# APM9328_MEMORY.net
KiCad netlist of a schematic drawn in Altium Designer
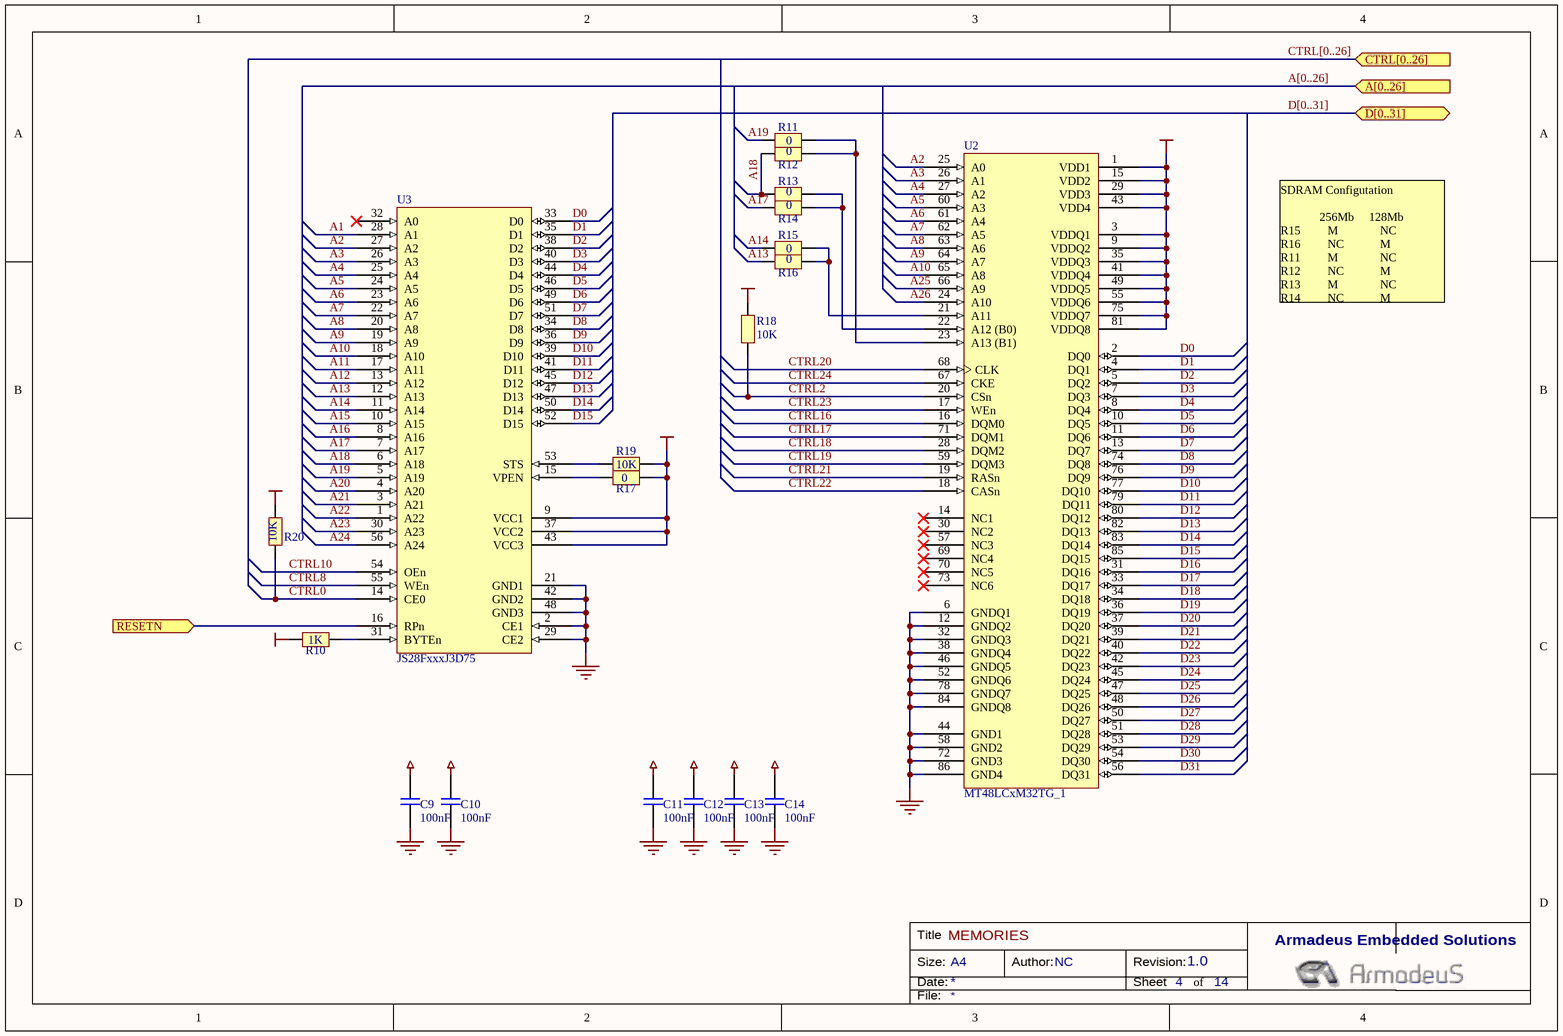
[diagram p0: APM9328_MEMORY.SchDoc]

(export (version "E")
  (design (tool "Eeschema 10.0.6"))
  (components
    (comp (ref "C9") (value "100nF") (footprint "0402") (libsource (lib "Misc") (part "Cap")))
    (comp (ref "C10") (value "100nF") (footprint "0402") (libsource (lib "Misc") (part "Cap")))
    (comp (ref "C11") (value "100nF") (footprint "0402") (libsource (lib "Misc") (part "Cap")))
    (comp (ref "C12") (value "100nF") (footprint "0402") (libsource (lib "Misc") (part "Cap")))
    (comp (ref "C13") (value "100nF") (footprint "0402") (libsource (lib "Misc") (part "Cap")))
    (comp (ref "C14") (value "100nF") (footprint "0402") (libsource (lib "Misc") (part "Cap")))
    (comp (ref "R10") (value "1K") (footprint "0402") (libsource (lib "*") (part "Res")))
    (comp (ref "R11") (value "0") (footprint "0402") (libsource (lib "*") (part "Res")))
    (comp (ref "R12") (value "0") (footprint "0402") (libsource (lib "*") (part "Res")))
    (comp (ref "R13") (value "0") (footprint "0402") (libsource (lib "*") (part "Res")))
    (comp (ref "R14") (value "0") (footprint "0402") (libsource (lib "*") (part "Res")))
    (comp (ref "R15") (value "0") (footprint "0402") (libsource (lib "*") (part "Res")))
    (comp (ref "R16") (value "0") (footprint "0402") (libsource (lib "*") (part "Res")))
    (comp (ref "R17") (value "0") (footprint "0402") (libsource (lib "*") (part "Res")))
    (comp (ref "R18") (value "10K") (footprint "0402") (libsource (lib "") (part "Res_1")))
    (comp (ref "R19") (value "10K") (footprint "0402") (libsource (lib "*") (part "Res")))
    (comp (ref "R20") (value "10K") (footprint "0402") (libsource (lib "") (part "Res_1")))
    (comp (ref "U2")
      (value "MT48LCxM32TG_1")
      (footprint "TSOP86-400")
      (description "SDRAM Memory")
      (fields (field (name "MANUFACTURER") "Micron") (field (name "PART NUMBER") "MT48LC8M32B2TG-6:GTR"))
      (libsource (lib "*") (part "MT48LCxM32TG_1"))
    )
    (comp (ref "U3")
      (value "JS28FxxxJ3D75")
      (footprint "TSOP56")
      (description "FLASH Memory")
      (fields (field (name "MANUFACTURER") "Intel") (field (name "PART NUMBER") "JS28F128J3D75"))
      (libsource (lib "*") (part "MT28FxxxJ3RG"))
    )
  )
  (nets
    (net (code "16") (name "+3V3") (class "Default")
      (node (ref "C10") (pin "2") (pintype "passive"))
      (node (ref "C11") (pin "2") (pintype "passive"))
      (node (ref "C12") (pin "2") (pintype "passive"))
      (node (ref "C13") (pin "2") (pintype "passive"))
      (node (ref "C14") (pin "2") (pintype "passive"))
      (node (ref "C9") (pin "2") (pintype "passive"))
      (node (ref "R10") (pin "1") (pintype "passive"))
      (node (ref "R17") (pin "2") (pintype "passive"))
      (node (ref "R18") (pin "2") (pintype "passive"))
      (node (ref "R19") (pin "2") (pintype "passive"))
      (node (ref "R20") (pin "2") (pintype "passive"))
      (node (ref "U2") (pin "1") (pinfunction "VDD1_1") (pintype "power_in"))
      (node (ref "U2") (pin "15") (pinfunction "VDD2_15") (pintype "power_in"))
      (node (ref "U2") (pin "29") (pinfunction "VDD3_29") (pintype "power_in"))
      (node (ref "U2") (pin "3") (pinfunction "VDDQ1_3") (pintype "power_in"))
      (node (ref "U2") (pin "35") (pinfunction "VDDQ3_35") (pintype "power_in"))
      (node (ref "U2") (pin "41") (pinfunction "VDDQ4_41") (pintype "power_in"))
      (node (ref "U2") (pin "43") (pinfunction "VDD4_43") (pintype "power_in"))
      (node (ref "U2") (pin "49") (pinfunction "VDDQ5_49") (pintype "power_in"))
      (node (ref "U2") (pin "55") (pinfunction "VDDQ6_55") (pintype "power_in"))
      (node (ref "U2") (pin "75") (pinfunction "VDDQ7_75") (pintype "power_in"))
      (node (ref "U2") (pin "81") (pinfunction "VDDQ8_81") (pintype "power_in"))
      (node (ref "U2") (pin "9") (pinfunction "VDDQ2_9") (pintype "power_in"))
      (node (ref "U3") (pin "37") (pinfunction "VCC2_37") (pintype "power_in"))
      (node (ref "U3") (pin "43") (pinfunction "VCC3_43") (pintype "power_in"))
      (node (ref "U3") (pin "9") (pinfunction "VCC1_9") (pintype "power_in"))
    )
    (net (code "17") (name "/A1") (class "Default")
      (node (ref "U3") (pin "28") (pinfunction "A1_28") (pintype "input"))
    )
    (net (code "18") (name "/A2") (class "Default")
      (node (ref "U2") (pin "25") (pinfunction "A0_25") (pintype "input"))
      (node (ref "U3") (pin "27") (pinfunction "A2_27") (pintype "input"))
    )
    (net (code "19") (name "/A3") (class "Default")
      (node (ref "U2") (pin "26") (pinfunction "A1_26") (pintype "input"))
      (node (ref "U3") (pin "26") (pinfunction "A3_26") (pintype "input"))
    )
    (net (code "20") (name "/A4") (class "Default")
      (node (ref "U2") (pin "27") (pinfunction "A2_27") (pintype "input"))
      (node (ref "U3") (pin "25") (pinfunction "A4_25") (pintype "input"))
    )
    (net (code "21") (name "/A5") (class "Default")
      (node (ref "U2") (pin "60") (pinfunction "A3_60") (pintype "input"))
      (node (ref "U3") (pin "24") (pinfunction "A5_24") (pintype "input"))
    )
    (net (code "22") (name "/A6") (class "Default")
      (node (ref "U2") (pin "61") (pinfunction "A4_61") (pintype "input"))
      (node (ref "U3") (pin "23") (pinfunction "A6_23") (pintype "input"))
    )
    (net (code "23") (name "/A7") (class "Default")
      (node (ref "U2") (pin "62") (pinfunction "A5_62") (pintype "input"))
      (node (ref "U3") (pin "22") (pinfunction "A7_22") (pintype "input"))
    )
    (net (code "24") (name "/A8") (class "Default")
      (node (ref "U2") (pin "63") (pinfunction "A6_63") (pintype "input"))
      (node (ref "U3") (pin "20") (pinfunction "A8_20") (pintype "input"))
    )
    (net (code "25") (name "/A9") (class "Default")
      (node (ref "U2") (pin "64") (pinfunction "A7_64") (pintype "input"))
      (node (ref "U3") (pin "19") (pinfunction "A9_19") (pintype "input"))
    )
    (net (code "26") (name "/A10") (class "Default")
      (node (ref "U2") (pin "65") (pinfunction "A8_65") (pintype "input"))
      (node (ref "U3") (pin "18") (pinfunction "A10_18") (pintype "input"))
    )
    (net (code "27") (name "/A11") (class "Default")
      (node (ref "U3") (pin "17") (pinfunction "A11_17") (pintype "input"))
    )
    (net (code "28") (name "/A12") (class "Default")
      (node (ref "U3") (pin "13") (pinfunction "A12_13") (pintype "input"))
    )
    (net (code "29") (name "/A13") (class "Default")
      (node (ref "R16") (pin "1") (pintype "passive"))
      (node (ref "U3") (pin "12") (pinfunction "A13_12") (pintype "input"))
    )
    (net (code "30") (name "/A14") (class "Default")
      (node (ref "R15") (pin "1") (pintype "passive"))
      (node (ref "U3") (pin "11") (pinfunction "A14_11") (pintype "input"))
    )
    (net (code "31") (name "/A15") (class "Default")
      (node (ref "U3") (pin "10") (pinfunction "A15_10") (pintype "input"))
    )
    (net (code "32") (name "/A16") (class "Default")
      (node (ref "U3") (pin "8") (pinfunction "A16_8") (pintype "input"))
    )
    (net (code "33") (name "/A17") (class "Default")
      (node (ref "R14") (pin "1") (pintype "passive"))
      (node (ref "U3") (pin "7") (pinfunction "A17_7") (pintype "input"))
    )
    (net (code "34") (name "/A18") (class "Default")
      (node (ref "R12") (pin "1") (pintype "passive"))
      (node (ref "R13") (pin "1") (pintype "passive"))
      (node (ref "U3") (pin "6") (pinfunction "A18_6") (pintype "input"))
    )
    (net (code "35") (name "/A19") (class "Default")
      (node (ref "R11") (pin "1") (pintype "passive"))
      (node (ref "U3") (pin "5") (pinfunction "A19_5") (pintype "input"))
    )
    (net (code "36") (name "/A20") (class "Default")
      (node (ref "U3") (pin "4") (pinfunction "A20_4") (pintype "input"))
    )
    (net (code "37") (name "/A21") (class "Default")
      (node (ref "U3") (pin "3") (pinfunction "A21_3") (pintype "input"))
    )
    (net (code "38") (name "/A22") (class "Default")
      (node (ref "U3") (pin "1") (pinfunction "A22_1") (pintype "input"))
    )
    (net (code "39") (name "/A23") (class "Default")
      (node (ref "U3") (pin "30") (pinfunction "A23_30") (pintype "input"))
    )
    (net (code "40") (name "/A24") (class "Default")
      (node (ref "U3") (pin "56") (pinfunction "A24_56") (pintype "input"))
    )
    (net (code "41") (name "/A25") (class "Default")
      (node (ref "U2") (pin "66") (pinfunction "A9_66") (pintype "input"))
    )
    (net (code "42") (name "/A26") (class "Default")
      (node (ref "U2") (pin "24") (pinfunction "A10_24") (pintype "input"))
    )
    (net (code "44") (name "/CTRL0") (class "Default")
      (node (ref "R20") (pin "1") (pintype "passive"))
      (node (ref "U3") (pin "14") (pinfunction "CE0_14") (pintype "input"))
    )
    (net (code "45") (name "/CTRL2") (class "Default")
      (node (ref "R18") (pin "1") (pintype "passive"))
      (node (ref "U2") (pin "20") (pinfunction "CSn_20") (pintype "input"))
    )
    (net (code "46") (name "/CTRL8") (class "Default")
      (node (ref "U3") (pin "55") (pinfunction "WEn_55") (pintype "input"))
    )
    (net (code "47") (name "/CTRL10") (class "Default")
      (node (ref "U3") (pin "54") (pinfunction "OEn_54") (pintype "input"))
    )
    (net (code "48") (name "/CTRL16") (class "Default")
      (node (ref "U2") (pin "16") (pinfunction "DQM0_16") (pintype "input"))
    )
    (net (code "49") (name "/CTRL17") (class "Default")
      (node (ref "U2") (pin "71") (pinfunction "DQM1_71") (pintype "input"))
    )
    (net (code "50") (name "/CTRL18") (class "Default")
      (node (ref "U2") (pin "28") (pinfunction "DQM2_28") (pintype "input"))
    )
    (net (code "51") (name "/CTRL19") (class "Default")
      (node (ref "U2") (pin "59") (pinfunction "DQM3_59") (pintype "input"))
    )
    (net (code "52") (name "/CTRL20") (class "Default")
      (node (ref "U2") (pin "68") (pinfunction "CLK_68") (pintype "input"))
    )
    (net (code "53") (name "/CTRL21") (class "Default")
      (node (ref "U2") (pin "19") (pinfunction "RASn_19") (pintype "input"))
    )
    (net (code "54") (name "/CTRL22") (class "Default")
      (node (ref "U2") (pin "18") (pinfunction "CASn_18") (pintype "input"))
    )
    (net (code "55") (name "/CTRL23") (class "Default")
      (node (ref "U2") (pin "17") (pinfunction "WEn_17") (pintype "input"))
    )
    (net (code "56") (name "/CTRL24") (class "Default")
      (node (ref "U2") (pin "67") (pinfunction "CKE_67") (pintype "input"))
    )
    (net (code "58") (name "/D0") (class "Default")
      (node (ref "U2") (pin "2") (pinfunction "DQ0_2") (pintype "bidirectional"))
      (node (ref "U3") (pin "33") (pinfunction "D0_33") (pintype "bidirectional"))
    )
    (net (code "59") (name "/D1") (class "Default")
      (node (ref "U2") (pin "4") (pinfunction "DQ1_4") (pintype "bidirectional"))
      (node (ref "U3") (pin "35") (pinfunction "D1_35") (pintype "bidirectional"))
    )
    (net (code "60") (name "/D2") (class "Default")
      (node (ref "U2") (pin "5") (pinfunction "DQ2_5") (pintype "bidirectional"))
      (node (ref "U3") (pin "38") (pinfunction "D2_38") (pintype "bidirectional"))
    )
    (net (code "61") (name "/D3") (class "Default")
      (node (ref "U2") (pin "7") (pinfunction "DQ3_7") (pintype "bidirectional"))
      (node (ref "U3") (pin "40") (pinfunction "D3_40") (pintype "bidirectional"))
    )
    (net (code "62") (name "/D4") (class "Default")
      (node (ref "U2") (pin "8") (pinfunction "DQ4_8") (pintype "bidirectional"))
      (node (ref "U3") (pin "44") (pinfunction "D4_44") (pintype "bidirectional"))
    )
    (net (code "63") (name "/D5") (class "Default")
      (node (ref "U2") (pin "10") (pinfunction "DQ5_10") (pintype "bidirectional"))
      (node (ref "U3") (pin "46") (pinfunction "D5_46") (pintype "bidirectional"))
    )
    (net (code "64") (name "/D6") (class "Default")
      (node (ref "U2") (pin "11") (pinfunction "DQ6_11") (pintype "bidirectional"))
      (node (ref "U3") (pin "49") (pinfunction "D6_49") (pintype "bidirectional"))
    )
    (net (code "65") (name "/D7") (class "Default")
      (node (ref "U2") (pin "13") (pinfunction "DQ7_13") (pintype "bidirectional"))
      (node (ref "U3") (pin "51") (pinfunction "D7_51") (pintype "bidirectional"))
    )
    (net (code "66") (name "/D8") (class "Default")
      (node (ref "U2") (pin "74") (pinfunction "DQ8_74") (pintype "bidirectional"))
      (node (ref "U3") (pin "34") (pinfunction "D8_34") (pintype "bidirectional"))
    )
    (net (code "67") (name "/D9") (class "Default")
      (node (ref "U2") (pin "76") (pinfunction "DQ9_76") (pintype "bidirectional"))
      (node (ref "U3") (pin "36") (pinfunction "D9_36") (pintype "bidirectional"))
    )
    (net (code "68") (name "/D10") (class "Default")
      (node (ref "U2") (pin "77") (pinfunction "DQ10_77") (pintype "bidirectional"))
      (node (ref "U3") (pin "39") (pinfunction "D10_39") (pintype "bidirectional"))
    )
    (net (code "69") (name "/D11") (class "Default")
      (node (ref "U2") (pin "79") (pinfunction "DQ11_79") (pintype "bidirectional"))
      (node (ref "U3") (pin "41") (pinfunction "D11_41") (pintype "bidirectional"))
    )
    (net (code "70") (name "/D12") (class "Default")
      (node (ref "U2") (pin "80") (pinfunction "DQ12_80") (pintype "bidirectional"))
      (node (ref "U3") (pin "45") (pinfunction "D12_45") (pintype "bidirectional"))
    )
    (net (code "71") (name "/D13") (class "Default")
      (node (ref "U2") (pin "82") (pinfunction "DQ13_82") (pintype "bidirectional"))
      (node (ref "U3") (pin "47") (pinfunction "D13_47") (pintype "bidirectional"))
    )
    (net (code "72") (name "/D14") (class "Default")
      (node (ref "U2") (pin "83") (pinfunction "DQ14_83") (pintype "bidirectional"))
      (node (ref "U3") (pin "50") (pinfunction "D14_50") (pintype "bidirectional"))
    )
    (net (code "73") (name "/D15") (class "Default")
      (node (ref "U2") (pin "85") (pinfunction "DQ15_85") (pintype "bidirectional"))
      (node (ref "U3") (pin "52") (pinfunction "D15_52") (pintype "bidirectional"))
    )
    (net (code "74") (name "/D16") (class "Default")
      (node (ref "U2") (pin "31") (pinfunction "DQ16_31") (pintype "bidirectional"))
    )
    (net (code "75") (name "/D17") (class "Default")
      (node (ref "U2") (pin "33") (pinfunction "DQ17_33") (pintype "bidirectional"))
    )
    (net (code "76") (name "/D18") (class "Default")
      (node (ref "U2") (pin "34") (pinfunction "DQ18_34") (pintype "bidirectional"))
    )
    (net (code "77") (name "/D19") (class "Default")
      (node (ref "U2") (pin "36") (pinfunction "DQ19_36") (pintype "bidirectional"))
    )
    (net (code "78") (name "/D20") (class "Default")
      (node (ref "U2") (pin "37") (pinfunction "DQ20_37") (pintype "bidirectional"))
    )
    (net (code "79") (name "/D21") (class "Default")
      (node (ref "U2") (pin "39") (pinfunction "DQ21_39") (pintype "bidirectional"))
    )
    (net (code "80") (name "/D22") (class "Default")
      (node (ref "U2") (pin "40") (pinfunction "DQ22_40") (pintype "bidirectional"))
    )
    (net (code "81") (name "/D23") (class "Default")
      (node (ref "U2") (pin "42") (pinfunction "DQ23_42") (pintype "bidirectional"))
    )
    (net (code "82") (name "/D24") (class "Default")
      (node (ref "U2") (pin "45") (pinfunction "DQ24_45") (pintype "bidirectional"))
    )
    (net (code "83") (name "/D25") (class "Default")
      (node (ref "U2") (pin "47") (pinfunction "DQ25_47") (pintype "bidirectional"))
    )
    (net (code "84") (name "/D26") (class "Default")
      (node (ref "U2") (pin "48") (pinfunction "DQ26_48") (pintype "bidirectional"))
    )
    (net (code "85") (name "/D27") (class "Default")
      (node (ref "U2") (pin "50") (pinfunction "DQ27_50") (pintype "bidirectional"))
    )
    (net (code "86") (name "/D28") (class "Default")
      (node (ref "U2") (pin "51") (pinfunction "DQ28_51") (pintype "bidirectional"))
    )
    (net (code "87") (name "/D29") (class "Default")
      (node (ref "U2") (pin "53") (pinfunction "DQ29_53") (pintype "bidirectional"))
    )
    (net (code "88") (name "/D30") (class "Default")
      (node (ref "U2") (pin "54") (pinfunction "DQ30_54") (pintype "bidirectional"))
    )
    (net (code "89") (name "/D31") (class "Default")
      (node (ref "U2") (pin "56") (pinfunction "DQ31_56") (pintype "bidirectional"))
    )
    (net (code "91") (name "/RESETN") (class "Default")
      (node (ref "U3") (pin "16") (pinfunction "RPn_16") (pintype "input"))
    )
    (net (code "92") (name "GND") (class "Default")
      (node (ref "C10") (pin "1") (pintype "passive"))
      (node (ref "C11") (pin "1") (pintype "passive"))
      (node (ref "C12") (pin "1") (pintype "passive"))
      (node (ref "C13") (pin "1") (pintype "passive"))
      (node (ref "C14") (pin "1") (pintype "passive"))
      (node (ref "C9") (pin "1") (pintype "passive"))
      (node (ref "U2") (pin "12") (pinfunction "GNDQ2_12") (pintype "power_in"))
      (node (ref "U2") (pin "32") (pinfunction "GNDQ3_32") (pintype "power_in"))
      (node (ref "U2") (pin "38") (pinfunction "GNDQ4_38") (pintype "power_in"))
      (node (ref "U2") (pin "44") (pinfunction "GND1_44") (pintype "power_in"))
      (node (ref "U2") (pin "46") (pinfunction "GNDQ5_46") (pintype "power_in"))
      (node (ref "U2") (pin "52") (pinfunction "GNDQ6_52") (pintype "power_in"))
      (node (ref "U2") (pin "58") (pinfunction "GND2_58") (pintype "power_in"))
      (node (ref "U2") (pin "6") (pinfunction "GNDQ1_6") (pintype "power_in"))
      (node (ref "U2") (pin "72") (pinfunction "GND3_72") (pintype "power_in"))
      (node (ref "U2") (pin "78") (pinfunction "GNDQ7_78") (pintype "power_in"))
      (node (ref "U2") (pin "84") (pinfunction "GNDQ8_84") (pintype "power_in"))
      (node (ref "U2") (pin "86") (pinfunction "GND4_86") (pintype "power_in"))
      (node (ref "U3") (pin "2") (pinfunction "CE1_2") (pintype "input"))
      (node (ref "U3") (pin "21") (pinfunction "GND1_21") (pintype "power_in"))
      (node (ref "U3") (pin "29") (pinfunction "CE2_29") (pintype "input"))
      (node (ref "U3") (pin "42") (pinfunction "GND2_42") (pintype "power_in"))
      (node (ref "U3") (pin "48") (pinfunction "GND3_48") (pintype "power_in"))
    )
    (net (code "93") (name "Net-(U2-A11)") (class "Default")
      (node (ref "R15") (pin "2") (pintype "passive"))
      (node (ref "R16") (pin "2") (pintype "passive"))
      (node (ref "U2") (pin "21") (pinfunction "A11_21") (pintype "input"))
    )
    (net (code "94") (name "Net-(U2-A12_(B0))") (class "Default")
      (node (ref "R13") (pin "2") (pintype "passive"))
      (node (ref "R14") (pin "2") (pintype "passive"))
      (node (ref "U2") (pin "22") (pinfunction "A12_(B0)_22") (pintype "input"))
    )
    (net (code "95") (name "Net-(U2-A13_(B1))") (class "Default")
      (node (ref "R11") (pin "2") (pintype "passive"))
      (node (ref "R12") (pin "2") (pintype "passive"))
      (node (ref "U2") (pin "23") (pinfunction "A13_(B1)_23") (pintype "input"))
    )
    (net (code "96") (name "Net-(U3-BYTEn)") (class "Default")
      (node (ref "R10") (pin "2") (pintype "passive"))
      (node (ref "U3") (pin "31") (pinfunction "BYTEn_31") (pintype "input"))
    )
    (net (code "97") (name "Net-(U3-STS)") (class "Default")
      (node (ref "R19") (pin "1") (pintype "passive"))
      (node (ref "U3") (pin "53") (pinfunction "STS_53") (pintype "input"))
    )
    (net (code "98") (name "Net-(U3-VPEN)") (class "Default")
      (node (ref "R17") (pin "1") (pintype "passive"))
      (node (ref "U3") (pin "15") (pinfunction "VPEN_15") (pintype "input"))
    )
    (net (code "99") (name "unconnected-(U2-NC1-Pad14)") (class "Default")
      (node (ref "U2") (pin "14") (pinfunction "NC1_14") (pintype "passive+no_connect"))
    )
    (net (code "100") (name "unconnected-(U2-NC2-Pad30)") (class "Default")
      (node (ref "U2") (pin "30") (pinfunction "NC2_30") (pintype "passive+no_connect"))
    )
    (net (code "101") (name "unconnected-(U2-NC3-Pad57)") (class "Default")
      (node (ref "U2") (pin "57") (pinfunction "NC3_57") (pintype "passive+no_connect"))
    )
    (net (code "102") (name "unconnected-(U2-NC4-Pad69)") (class "Default")
      (node (ref "U2") (pin "69") (pinfunction "NC4_69") (pintype "passive+no_connect"))
    )
    (net (code "103") (name "unconnected-(U2-NC5-Pad70)") (class "Default")
      (node (ref "U2") (pin "70") (pinfunction "NC5_70") (pintype "passive+no_connect"))
    )
    (net (code "104") (name "unconnected-(U2-NC6-Pad73)") (class "Default")
      (node (ref "U2") (pin "73") (pinfunction "NC6_73") (pintype "passive+no_connect"))
    )
    (net (code "105") (name "unconnected-(U3-A0-Pad32)") (class "Default")
      (node (ref "U3") (pin "32") (pinfunction "A0_32") (pintype "input+no_connect"))
    )
  )
)
